# Moteino.net
KiCad netlist of a schematic drawn in EAGLE
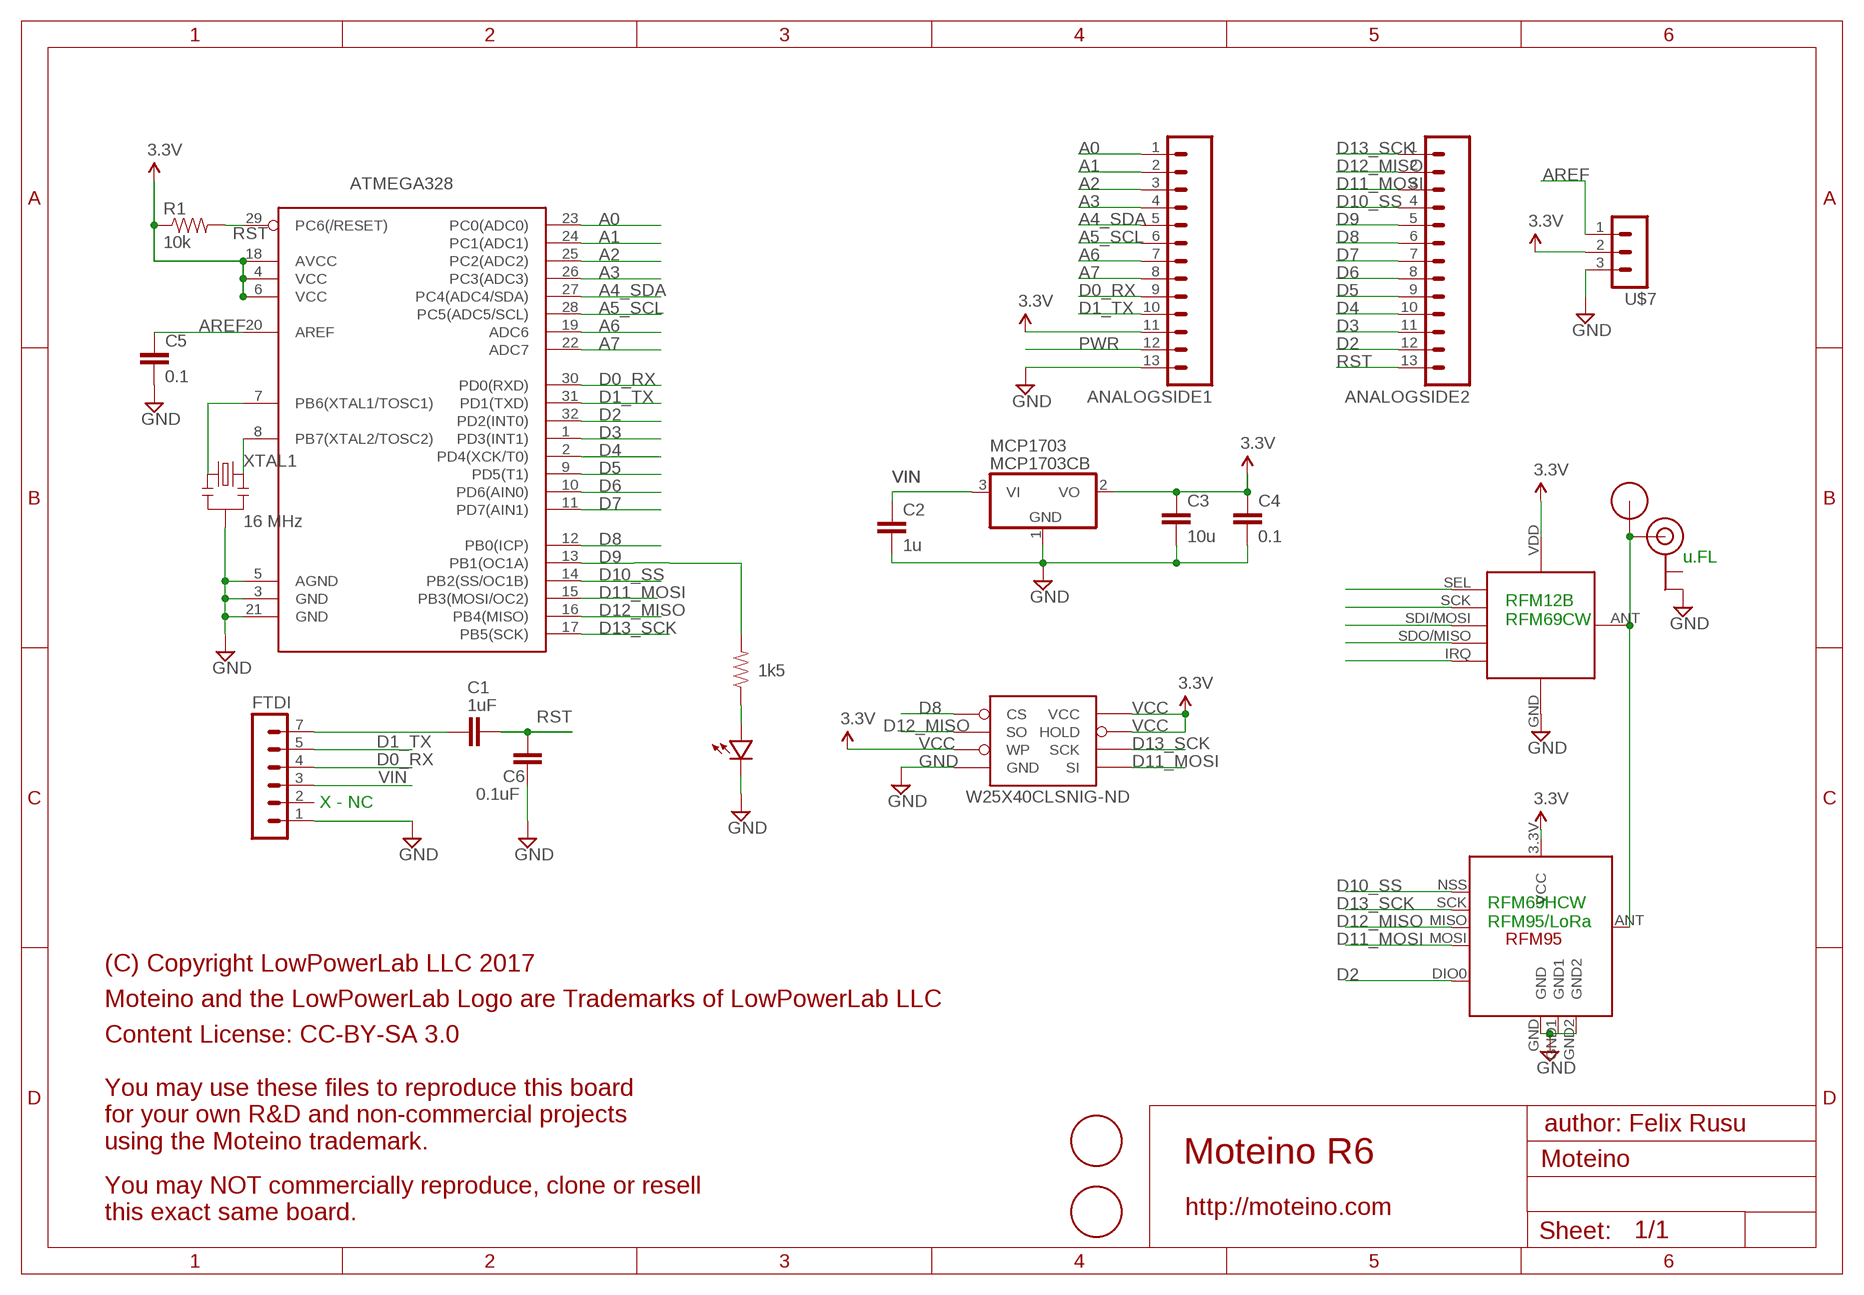
[diagram p0: schematic, sheet 1]

(export (version "E")
  (design (tool "Eeschema 10.0.6"))
  (components
    (comp (ref "ANALOGSIDE1")
      (value "HDR_13PINTHIN_RINGS")
      (footprint "eagle-import:1X13_THINRINGS")
      (libsource (lib "eagle-import") (part "HDR_13PINTHIN_RINGS"))
    )
    (comp (ref "ANALOGSIDE2")
      (value "HDR_13PINTHIN_RINGS")
      (footprint "eagle-import:1X13_THINRINGS")
      (libsource (lib "eagle-import") (part "HDR_13PINTHIN_RINGS"))
    )
    (comp (ref "ATMEGA328")
      (value "ATMega-328")
      (footprint "eagle-import:TQFP32-08")
      (libsource (lib "eagle-import") (part "ATMEGA168/328TQFP32"))
    )
    (comp (ref "C1")
      (value "1uF")
      (footprint "eagle-import:0603-CAP")
      (libsource (lib "eagle-import") (part "CAP0603-CAP"))
    )
    (comp (ref "C2")
      (value "1u")
      (footprint "eagle-import:0603-CAP")
      (libsource (lib "eagle-import") (part "CAP0603-CAP"))
    )
    (comp (ref "C3")
      (value "10u")
      (footprint "eagle-import:0805-CAP")
      (libsource (lib "eagle-import") (part "CAP0805-CAP"))
    )
    (comp (ref "C4")
      (value "0.1")
      (footprint "eagle-import:0603-CAP")
      (libsource (lib "eagle-import") (part "CAP0603-CAP"))
    )
    (comp (ref "C5")
      (value "0.1")
      (footprint "eagle-import:0603-CAP")
      (libsource (lib "eagle-import") (part "CAP0603-CAP"))
    )
    (comp (ref "C6")
      (value "0.1uF")
      (footprint "eagle-import:0603-CAP")
      (libsource (lib "eagle-import") (part "CAP0603-CAP"))
    )
    (comp (ref "FTDI")
      (value "HDR_6PINTHINRINGS")
      (footprint "eagle-import:1X06_NS_THINRINGS")
      (libsource (lib "eagle-import") (part "HDR_6PINTHINRINGS"))
    )
    (comp (ref "LED")
      (value "LED0603")
      (footprint "eagle-import:0603-LED")
      (libsource (lib "eagle-import") (part "LED0603"))
    )
    (comp (ref "MCP1703")
      (value "MCP1703CB")
      (footprint "eagle-import:SOT23")
      (libsource (lib "eagle-import") (part "MCP1703CB"))
    )
    (comp (ref "R1")
      (value "10k")
      (footprint "eagle-import:0603-RES")
      (libsource (lib "eagle-import") (part "RESISTOR0603-RES"))
    )
    (comp (ref "R2")
      (value "1k5")
      (footprint "eagle-import:0603-RES")
      (libsource (lib "eagle-import") (part "RESISTOR0603-RES"))
    )
    (comp (ref "U$1")
      (value "RFM12B_ANTENNA\"\"")
      (footprint "eagle-import:RFM12B-ANTENNA")
      (libsource (lib "eagle-import") (part "RFM12B_ANTENNA{dblquote}{dblquote}"))
    )
    (comp (ref "U$2")
      (value "RFM95LONGER")
      (footprint "eagle-import:RFM95_LONGER")
      (libsource (lib "eagle-import") (part "RFM95LONGER"))
    )
    (comp (ref "U$4")
      (value "U.FL")
      (footprint "eagle-import:U.FL")
      (libsource (lib "eagle-import") (part "U.FL"))
    )
    (comp (ref "U$5")
      (value "FIDUCIAL1.5MM")
      (footprint "eagle-import:FIDUCIAL_1.5MM")
      (libsource (lib "eagle-import") (part "FIDUCIAL1.5MM"))
    )
    (comp (ref "U$6")
      (value "FIDUCIAL1.5MM")
      (footprint "eagle-import:FIDUCIAL_1.5MM")
      (libsource (lib "eagle-import") (part "FIDUCIAL1.5MM"))
    )
    (comp (ref "U$7")
      (value "HDR_3PINTHINRINGS")
      (footprint "eagle-import:1X03_NS_THINRINGS")
      (libsource (lib "eagle-import") (part "HDR_3PINTHINRINGS"))
    )
    (comp (ref "U$8")
      (value "RFM12B_MINPADS")
      (footprint "eagle-import:RFM12B-MINPADS")
      (libsource (lib "eagle-import") (part "RFM12B_MINPADS"))
    )
    (comp (ref "W25X40CLSNIG-ND")
      (value "AT25F512BJEDEC_3.9MM")
      (footprint "eagle-import:SO08")
      (libsource (lib "eagle-import") (part "AT25F512BJEDEC_3.9MM"))
    )
    (comp (ref "XTAL1")
      (value "16 MHz")
      (footprint "eagle-import:RESONATOR-SMD")
      (libsource (lib "eagle-import") (part "RESONATORSMD"))
    )
  )
  (nets
    (net (code "1") (name "/A0") (class "Default")
      (node (ref "ANALOGSIDE1") (pin "1") (pinfunction "1_1") (pintype "passive"))
      (node (ref "ATMEGA328") (pin "23") (pinfunction "PC0(ADC0)_23") (pintype "bidirectional"))
    )
    (net (code "2") (name "/A1") (class "Default")
      (node (ref "ANALOGSIDE1") (pin "2") (pinfunction "2_2") (pintype "passive"))
      (node (ref "ATMEGA328") (pin "24") (pinfunction "PC1(ADC1)_24") (pintype "bidirectional"))
    )
    (net (code "3") (name "/A2") (class "Default")
      (node (ref "ANALOGSIDE1") (pin "3") (pinfunction "3_3") (pintype "passive"))
      (node (ref "ATMEGA328") (pin "25") (pinfunction "PC2(ADC2)_25") (pintype "bidirectional"))
    )
    (net (code "4") (name "/A3") (class "Default")
      (node (ref "ANALOGSIDE1") (pin "4") (pinfunction "4_4") (pintype "passive"))
      (node (ref "ATMEGA328") (pin "26") (pinfunction "PC3(ADC3)_26") (pintype "bidirectional"))
    )
    (net (code "5") (name "/A4_SDA") (class "Default")
      (node (ref "ANALOGSIDE1") (pin "5") (pinfunction "5_5") (pintype "passive"))
      (node (ref "ATMEGA328") (pin "27") (pinfunction "PC4(ADC4/SDA)_27") (pintype "bidirectional"))
    )
    (net (code "6") (name "/A5_SCL") (class "Default")
      (node (ref "ANALOGSIDE1") (pin "6") (pinfunction "6_6") (pintype "passive"))
      (node (ref "ATMEGA328") (pin "28") (pinfunction "PC5(ADC5/SCL)_28") (pintype "bidirectional"))
    )
    (net (code "7") (name "/A6") (class "Default")
      (node (ref "ANALOGSIDE1") (pin "7") (pinfunction "7_7") (pintype "passive"))
      (node (ref "ATMEGA328") (pin "19") (pinfunction "ADC6_19") (pintype "bidirectional"))
    )
    (net (code "8") (name "/A7") (class "Default")
      (node (ref "ANALOGSIDE1") (pin "8") (pinfunction "8_8") (pintype "passive"))
      (node (ref "ATMEGA328") (pin "22") (pinfunction "ADC7_22") (pintype "bidirectional"))
    )
    (net (code "9") (name "/AREF") (class "Default")
      (node (ref "ATMEGA328") (pin "20") (pinfunction "AREF_20") (pintype "bidirectional"))
      (node (ref "C5") (pin "1") (pinfunction "1_1") (pintype "passive"))
      (node (ref "U$7") (pin "1") (pinfunction "1_1") (pintype "passive"))
    )
    (net (code "10") (name "/D0_RX") (class "Default")
      (node (ref "ANALOGSIDE1") (pin "9") (pinfunction "9_9") (pintype "passive"))
      (node (ref "ATMEGA328") (pin "30") (pinfunction "PD0(RXD)_30") (pintype "bidirectional"))
      (node (ref "FTDI") (pin "4") (pinfunction "4_4") (pintype "passive"))
    )
    (net (code "11") (name "/D1_TX") (class "Default")
      (node (ref "ANALOGSIDE1") (pin "10") (pinfunction "10_10") (pintype "passive"))
      (node (ref "ATMEGA328") (pin "31") (pinfunction "PD1(TXD)_31") (pintype "bidirectional"))
      (node (ref "FTDI") (pin "5") (pinfunction "5_5") (pintype "passive"))
    )
    (net (code "12") (name "/D2") (class "Default")
      (node (ref "ANALOGSIDE2") (pin "12") (pinfunction "12_12") (pintype "passive"))
      (node (ref "ATMEGA328") (pin "32") (pinfunction "PD2(INT0)_32") (pintype "bidirectional"))
      (node (ref "U$2") (pin "DIO0") (pinfunction "DIO0_DIO0") (pintype "open_collector"))
      (node (ref "U$8") (pin "IRQ") (pinfunction "IRQ_IRQ") (pintype "bidirectional"))
    )
    (net (code "13") (name "/D3") (class "Default")
      (node (ref "ANALOGSIDE2") (pin "11") (pinfunction "11_11") (pintype "passive"))
      (node (ref "ATMEGA328") (pin "1") (pinfunction "PD3(INT1)_1") (pintype "bidirectional"))
    )
    (net (code "14") (name "/D4") (class "Default")
      (node (ref "ANALOGSIDE2") (pin "10") (pinfunction "10_10") (pintype "passive"))
      (node (ref "ATMEGA328") (pin "2") (pinfunction "PD4(XCK/T0)_2") (pintype "bidirectional"))
    )
    (net (code "15") (name "/D5") (class "Default")
      (node (ref "ANALOGSIDE2") (pin "9") (pinfunction "9_9") (pintype "passive"))
      (node (ref "ATMEGA328") (pin "9") (pinfunction "PD5(T1)_9") (pintype "bidirectional"))
    )
    (net (code "16") (name "/D6") (class "Default")
      (node (ref "ANALOGSIDE2") (pin "8") (pinfunction "8_8") (pintype "passive"))
      (node (ref "ATMEGA328") (pin "10") (pinfunction "PD6(AIN0)_10") (pintype "bidirectional"))
    )
    (net (code "17") (name "/D7") (class "Default")
      (node (ref "ANALOGSIDE2") (pin "7") (pinfunction "7_7") (pintype "passive"))
      (node (ref "ATMEGA328") (pin "11") (pinfunction "PD7(AIN1)_11") (pintype "bidirectional"))
    )
    (net (code "18") (name "/D8") (class "Default")
      (node (ref "ANALOGSIDE2") (pin "6") (pinfunction "6_6") (pintype "passive"))
      (node (ref "ATMEGA328") (pin "12") (pinfunction "PB0(ICP)_12") (pintype "bidirectional"))
      (node (ref "W25X40CLSNIG-ND") (pin "1_CS") (pinfunction "CS_1_CS") (pintype "bidirectional"))
    )
    (net (code "19") (name "/D9") (class "Default")
      (node (ref "ANALOGSIDE2") (pin "5") (pinfunction "5_5") (pintype "passive"))
      (node (ref "ATMEGA328") (pin "13") (pinfunction "PB1(OC1A)_13") (pintype "bidirectional"))
      (node (ref "R2") (pin "2") (pinfunction "2_2") (pintype "passive"))
    )
    (net (code "20") (name "/D10_SS") (class "Default")
      (node (ref "ANALOGSIDE2") (pin "4") (pinfunction "4_4") (pintype "passive"))
      (node (ref "ATMEGA328") (pin "14") (pinfunction "PB2(SS/OC1B)_14") (pintype "bidirectional"))
      (node (ref "U$2") (pin "NSS") (pinfunction "SEL_NSS") (pintype "input"))
      (node (ref "U$8") (pin "SEL") (pinfunction "SEL_SEL") (pintype "bidirectional"))
    )
    (net (code "21") (name "/D11_MOSI") (class "Default")
      (node (ref "ANALOGSIDE2") (pin "3") (pinfunction "3_3") (pintype "passive"))
      (node (ref "ATMEGA328") (pin "15") (pinfunction "PB3(MOSI/OC2)_15") (pintype "bidirectional"))
      (node (ref "U$2") (pin "MOSI") (pinfunction "MOSI_MOSI") (pintype "output"))
      (node (ref "U$8") (pin "SDI/MOSI") (pinfunction "SDI/MOSI_SDI/MOSI") (pintype "bidirectional"))
      (node (ref "W25X40CLSNIG-ND") (pin "5_SI") (pinfunction "SI_5_SI") (pintype "bidirectional"))
    )
    (net (code "22") (name "/D12_MISO") (class "Default")
      (node (ref "ANALOGSIDE2") (pin "2") (pinfunction "2_2") (pintype "passive"))
      (node (ref "ATMEGA328") (pin "16") (pinfunction "PB4(MISO)_16") (pintype "bidirectional"))
      (node (ref "U$2") (pin "MISO") (pinfunction "MISO_MISO") (pintype "input"))
      (node (ref "U$8") (pin "SDO/MISO") (pinfunction "SDO/MISO_SDO/MISO") (pintype "bidirectional"))
      (node (ref "W25X40CLSNIG-ND") (pin "2_SO") (pinfunction "SO_2_SO") (pintype "bidirectional"))
    )
    (net (code "23") (name "/D13_SCK") (class "Default")
      (node (ref "ANALOGSIDE2") (pin "1") (pinfunction "1_1") (pintype "passive"))
      (node (ref "ATMEGA328") (pin "17") (pinfunction "PB5(SCK)_17") (pintype "bidirectional"))
      (node (ref "U$2") (pin "SCK") (pinfunction "SCK_SCK") (pintype "input"))
      (node (ref "U$8") (pin "SCK") (pinfunction "SCK_SCK") (pintype "bidirectional"))
      (node (ref "W25X40CLSNIG-ND") (pin "6_SCK") (pinfunction "SCK_6_SCK") (pintype "bidirectional"))
    )
    (net (code "24") (name "/PWR") (class "Default")
      (node (ref "ANALOGSIDE1") (pin "12") (pinfunction "12_12") (pintype "passive"))
    )
    (net (code "25") (name "/RST") (class "Default")
      (node (ref "ANALOGSIDE2") (pin "13") (pinfunction "13_13") (pintype "passive"))
      (node (ref "ATMEGA328") (pin "29") (pinfunction "PC6(/RESET)_29") (pintype "bidirectional"))
      (node (ref "C1") (pin "1") (pinfunction "1_1") (pintype "passive"))
      (node (ref "C6") (pin "1") (pinfunction "1_1") (pintype "passive"))
      (node (ref "R1") (pin "2") (pinfunction "2_2") (pintype "passive"))
    )
    (net (code "26") (name "/VIN") (class "Default")
      (node (ref "C2") (pin "1") (pinfunction "1_1") (pintype "passive"))
      (node (ref "FTDI") (pin "3") (pinfunction "3_3") (pintype "passive"))
      (node (ref "MCP1703") (pin "3") (pinfunction "VI_3") (pintype "input"))
    )
    (net (code "27") (name "3.3V") (class "Default")
      (node (ref "ANALOGSIDE1") (pin "11") (pinfunction "11_11") (pintype "passive"))
      (node (ref "ATMEGA328") (pin "18") (pinfunction "AVCC_18") (pintype "bidirectional"))
      (node (ref "ATMEGA328") (pin "4") (pinfunction "VCC_4") (pintype "bidirectional"))
      (node (ref "ATMEGA328") (pin "6") (pinfunction "VCC_6") (pintype "bidirectional"))
      (node (ref "C3") (pin "1") (pinfunction "1_1") (pintype "passive"))
      (node (ref "C4") (pin "1") (pinfunction "1_1") (pintype "passive"))
      (node (ref "MCP1703") (pin "2") (pinfunction "VO_2") (pintype "passive"))
      (node (ref "R1") (pin "1") (pinfunction "1_1") (pintype "passive"))
      (node (ref "U$2") (pin "3.3V") (pinfunction "VCC_3.3V") (pintype "power_in"))
      (node (ref "U$7") (pin "2") (pinfunction "2_2") (pintype "passive"))
      (node (ref "U$8") (pin "VDD") (pinfunction "VDD_VDD") (pintype "bidirectional"))
      (node (ref "W25X40CLSNIG-ND") (pin "3_WP") (pinfunction "WP_3_WP") (pintype "bidirectional"))
      (node (ref "W25X40CLSNIG-ND") (pin "7_HOLD") (pinfunction "HOLD_7_HOLD") (pintype "bidirectional"))
      (node (ref "W25X40CLSNIG-ND") (pin "8_VCC") (pinfunction "VCC_8_VCC") (pintype "bidirectional"))
    )
    (net (code "28") (name "GND") (class "Default")
      (node (ref "ANALOGSIDE1") (pin "13") (pinfunction "13_13") (pintype "passive"))
      (node (ref "ATMEGA328") (pin "21") (pinfunction "GND_21") (pintype "bidirectional"))
      (node (ref "ATMEGA328") (pin "3") (pinfunction "GND_3") (pintype "bidirectional"))
      (node (ref "ATMEGA328") (pin "5") (pinfunction "AGND_5") (pintype "bidirectional"))
      (node (ref "C2") (pin "2") (pinfunction "2_2") (pintype "passive"))
      (node (ref "C3") (pin "2") (pinfunction "2_2") (pintype "passive"))
      (node (ref "C4") (pin "2") (pinfunction "2_2") (pintype "passive"))
      (node (ref "C5") (pin "2") (pinfunction "2_2") (pintype "passive"))
      (node (ref "C6") (pin "2") (pinfunction "2_2") (pintype "passive"))
      (node (ref "FTDI") (pin "1") (pinfunction "1_1") (pintype "passive"))
      (node (ref "LED") (pin "MINUS") (pinfunction "MINUS_MINUS") (pintype "passive"))
      (node (ref "MCP1703") (pin "1") (pinfunction "GND_1") (pintype "passive"))
      (node (ref "U$2") (pin "GND") (pinfunction "GND_GND") (pintype "power_in"))
      (node (ref "U$2") (pin "GND1") (pinfunction "GND1_GND1") (pintype "power_in"))
      (node (ref "U$2") (pin "GND2") (pinfunction "GND2_GND2") (pintype "power_in"))
      (node (ref "U$4") (pin "GND2") (pinfunction "GND_GND2") (pintype "bidirectional"))
      (node (ref "U$7") (pin "3") (pinfunction "3_3") (pintype "passive"))
      (node (ref "U$8") (pin "GND") (pinfunction "GND_GND") (pintype "bidirectional"))
      (node (ref "W25X40CLSNIG-ND") (pin "4_GND") (pinfunction "GND_4_GND") (pintype "bidirectional"))
      (node (ref "XTAL1") (pin "2") (pinfunction "2_2") (pintype "passive"))
    )
    (net (code "29") (name "Net-(ATMEGA328-PB6(XTAL1{slash}TOSC1))") (class "Default")
      (node (ref "ATMEGA328") (pin "7") (pinfunction "PB6(XTAL1/TOSC1)_7") (pintype "bidirectional"))
      (node (ref "XTAL1") (pin "1") (pinfunction "1_1") (pintype "passive"))
    )
    (net (code "30") (name "Net-(ATMEGA328-PB7(XTAL2{slash}TOSC2))") (class "Default")
      (node (ref "ATMEGA328") (pin "8") (pinfunction "PB7(XTAL2/TOSC2)_8") (pintype "bidirectional"))
      (node (ref "XTAL1") (pin "3") (pinfunction "3_3") (pintype "passive"))
    )
    (net (code "31") (name "Net-(FTDI-6)") (class "Default")
      (node (ref "C1") (pin "2") (pinfunction "2_2") (pintype "passive"))
      (node (ref "FTDI") (pin "7") (pinfunction "6_7") (pintype "passive"))
    )
    (net (code "32") (name "Net-(LED-PadPLUS)") (class "Default")
      (node (ref "LED") (pin "PLUS") (pinfunction "PLUS_PLUS") (pintype "passive"))
      (node (ref "R2") (pin "1") (pinfunction "1_1") (pintype "passive"))
    )
    (net (code "33") (name "Net-(U$1-1)") (class "Default")
      (node (ref "U$1") (pin "P$1") (pinfunction "1_P$1") (pintype "bidirectional"))
      (node (ref "U$2") (pin "ANT") (pinfunction "ANT_ANT") (pintype "passive"))
      (node (ref "U$4") (pin "SIGNAL") (pinfunction "SIGNAL_SIGNAL") (pintype "bidirectional"))
      (node (ref "U$8") (pin "ANT") (pinfunction "ANT_ANT") (pintype "bidirectional"))
    )
    (net (code "34") (name "unconnected-(FTDI-Pad2)") (class "Default")
      (node (ref "FTDI") (pin "2") (pinfunction "2_2") (pintype "passive"))
    )
    (net (code "35") (name "unconnected-(U$4-GND-PadGND1)") (class "Default")
      (node (ref "U$4") (pin "GND1") (pinfunction "GND_GND1") (pintype "bidirectional"))
    )
    (net (code "36") (name "unconnected-(U$5-FIDUCIAL-PadP$1)") (class "Default")
      (node (ref "U$5") (pin "P$1") (pinfunction "FIDUCIAL_P$1") (pintype "bidirectional"))
    )
    (net (code "37") (name "unconnected-(U$6-FIDUCIAL-PadP$1)") (class "Default")
      (node (ref "U$6") (pin "P$1") (pinfunction "FIDUCIAL_P$1") (pintype "bidirectional"))
    )
  )
)
